# FSR_amp_v0_1.net
KiCad netlist of a schematic drawn in EAGLE
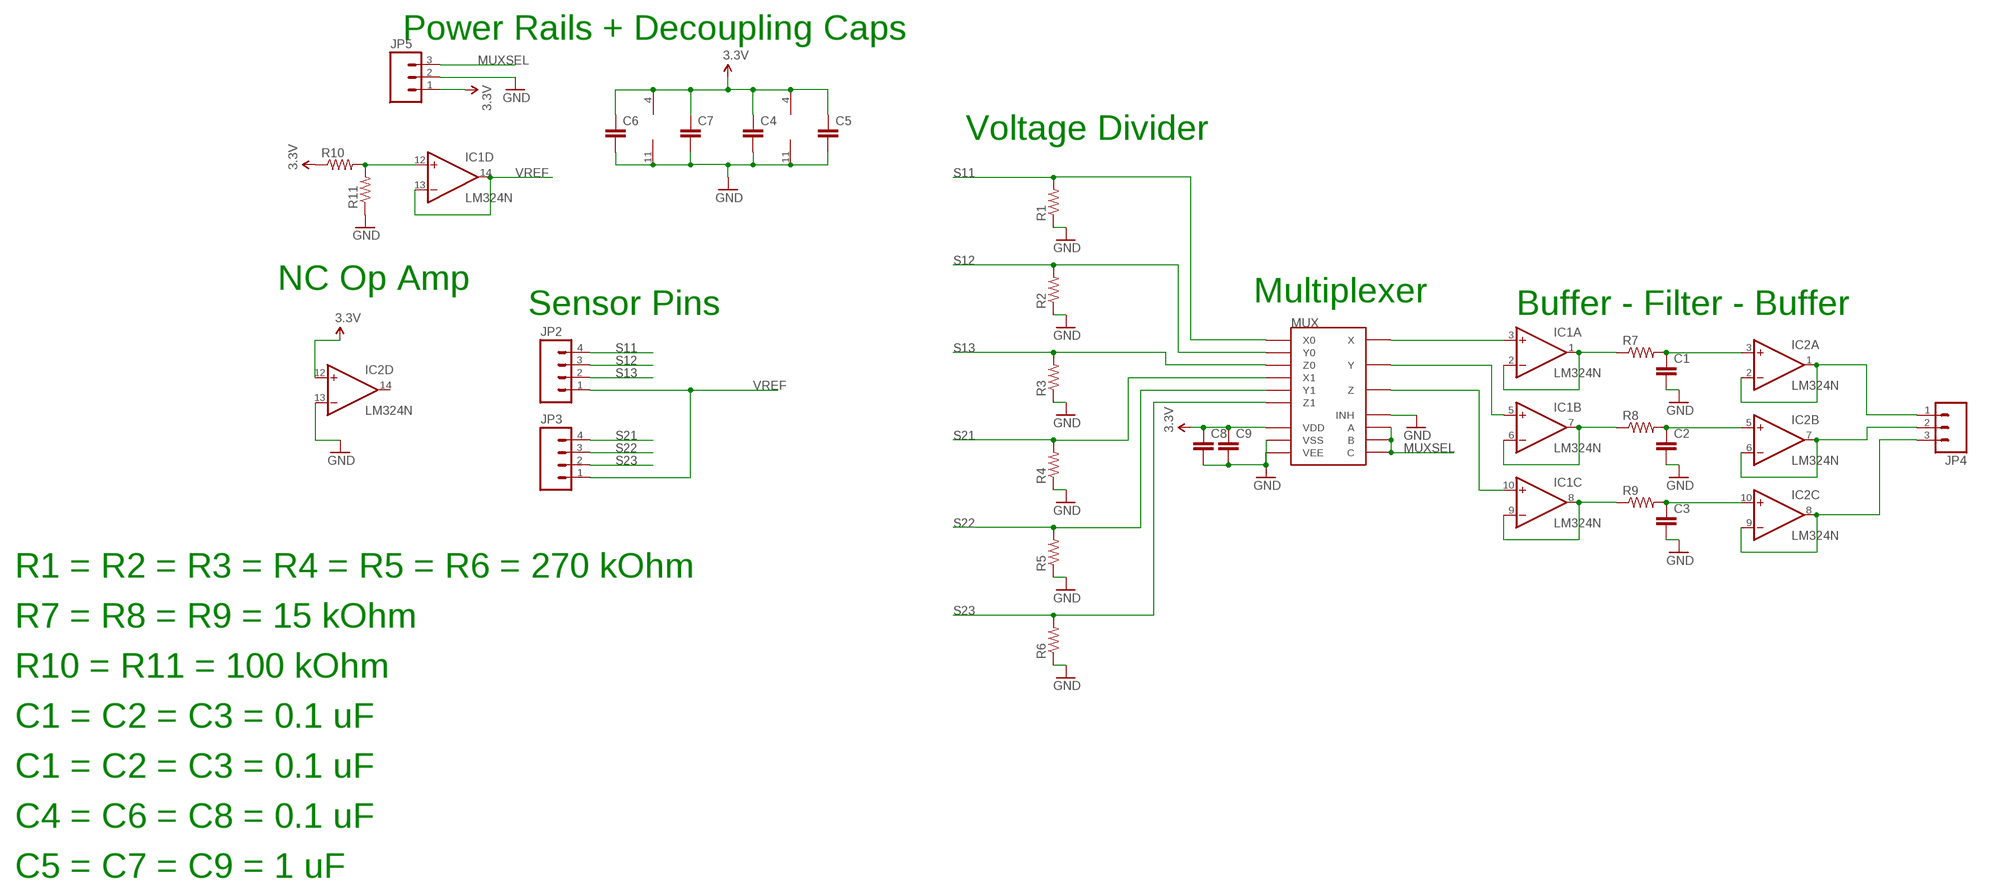
[diagram p0: schematic, sheet 1]

(export (version "E")
  (design (tool "Eeschema 10.0.6"))
  (components
    (comp (ref "C1")
      (value "CAPPTH")
      (footprint "eagle-import:CAP-PTH-SMALL")
      (libsource (lib "eagle-import") (part "CAPPTH"))
    )
    (comp (ref "C2")
      (value "CAPPTH")
      (footprint "eagle-import:CAP-PTH-SMALL")
      (libsource (lib "eagle-import") (part "CAPPTH"))
    )
    (comp (ref "C3")
      (value "CAPPTH")
      (footprint "eagle-import:CAP-PTH-SMALL")
      (libsource (lib "eagle-import") (part "CAPPTH"))
    )
    (comp (ref "C4")
      (value "CAPPTH")
      (footprint "eagle-import:CAP-PTH-SMALL")
      (libsource (lib "eagle-import") (part "CAPPTH"))
    )
    (comp (ref "C5")
      (value "CAPPTH")
      (footprint "eagle-import:CAP-PTH-SMALL")
      (libsource (lib "eagle-import") (part "CAPPTH"))
    )
    (comp (ref "C6")
      (value "CAPPTH")
      (footprint "eagle-import:CAP-PTH-SMALL")
      (libsource (lib "eagle-import") (part "CAPPTH"))
    )
    (comp (ref "C7")
      (value "CAPPTH")
      (footprint "eagle-import:CAP-PTH-SMALL")
      (libsource (lib "eagle-import") (part "CAPPTH"))
    )
    (comp (ref "C8")
      (value "CAPPTH")
      (footprint "eagle-import:CAP-PTH-SMALL")
      (libsource (lib "eagle-import") (part "CAPPTH"))
    )
    (comp (ref "C9")
      (value "CAPPTH")
      (footprint "eagle-import:CAP-PTH-SMALL")
      (libsource (lib "eagle-import") (part "CAPPTH"))
    )
    (comp (ref "IC1")
      (value "LM324N")
      (footprint "eagle-import:DIL14")
      (libsource (lib "eagle-import") (part "LM324N"))
    )
    (comp (ref "IC2")
      (value "LM324N")
      (footprint "eagle-import:DIL14")
      (libsource (lib "eagle-import") (part "LM324N"))
    )
    (comp (ref "JP2")
      (value "M04POLAR")
      (footprint "eagle-import:MOLEX-1X4")
      (libsource (lib "eagle-import") (part "M04POLAR"))
    )
    (comp (ref "JP3")
      (value "M04POLAR")
      (footprint "eagle-import:MOLEX-1X4")
      (libsource (lib "eagle-import") (part "M04POLAR"))
    )
    (comp (ref "JP4")
      (value "M03POLAR")
      (footprint "eagle-import:MOLEX-1X3")
      (libsource (lib "eagle-import") (part "M03POLAR"))
    )
    (comp (ref "JP5")
      (value "M03POLAR")
      (footprint "eagle-import:MOLEX-1X3")
      (libsource (lib "eagle-import") (part "M03POLAR"))
    )
    (comp (ref "MUX")
      (value "MC14053BCPDIL16")
      (footprint "eagle-import:DIL16")
      (libsource (lib "eagle-import") (part "MC14053BCPDIL16"))
    )
    (comp (ref "R1")
      (value "R-US_0207/10")
      (footprint "eagle-import:0207_10")
      (libsource (lib "eagle-import") (part "R-US_0207/10"))
    )
    (comp (ref "R2")
      (value "R-US_0207/10")
      (footprint "eagle-import:0207_10")
      (libsource (lib "eagle-import") (part "R-US_0207/10"))
    )
    (comp (ref "R3")
      (value "R-US_0207/10")
      (footprint "eagle-import:0207_10")
      (libsource (lib "eagle-import") (part "R-US_0207/10"))
    )
    (comp (ref "R4")
      (value "R-US_0207/10")
      (footprint "eagle-import:0207_10")
      (libsource (lib "eagle-import") (part "R-US_0207/10"))
    )
    (comp (ref "R5")
      (value "R-US_0207/10")
      (footprint "eagle-import:0207_10")
      (libsource (lib "eagle-import") (part "R-US_0207/10"))
    )
    (comp (ref "R6")
      (value "R-US_0207/10")
      (footprint "eagle-import:0207_10")
      (libsource (lib "eagle-import") (part "R-US_0207/10"))
    )
    (comp (ref "R7")
      (value "R-US_0207/10")
      (footprint "eagle-import:0207_10")
      (libsource (lib "eagle-import") (part "R-US_0207/10"))
    )
    (comp (ref "R8")
      (value "R-US_0207/10")
      (footprint "eagle-import:0207_10")
      (libsource (lib "eagle-import") (part "R-US_0207/10"))
    )
    (comp (ref "R9")
      (value "R-US_0207/10")
      (footprint "eagle-import:0207_10")
      (libsource (lib "eagle-import") (part "R-US_0207/10"))
    )
    (comp (ref "R10")
      (value "R-US_0207/10")
      (footprint "eagle-import:0207_10")
      (libsource (lib "eagle-import") (part "R-US_0207/10"))
    )
    (comp (ref "R11")
      (value "R-US_0207/10")
      (footprint "eagle-import:0207_10")
      (libsource (lib "eagle-import") (part "R-US_0207/10"))
    )
  )
  (nets
    (net (code "1") (name "/MUXSEL") (class "Default")
      (node (ref "JP5") (pin "3") (pinfunction "3_3") (pintype "passive"))
      (node (ref "MUX") (pin "10") (pinfunction "B_10") (pintype "bidirectional"))
      (node (ref "MUX") (pin "11") (pinfunction "A_11") (pintype "bidirectional"))
      (node (ref "MUX") (pin "9") (pinfunction "C_9") (pintype "bidirectional"))
    )
    (net (code "2") (name "/S11") (class "Default")
      (node (ref "JP2") (pin "4") (pinfunction "4_4") (pintype "passive"))
      (node (ref "MUX") (pin "12") (pinfunction "X0_12") (pintype "bidirectional"))
      (node (ref "R1") (pin "2") (pinfunction "2_2") (pintype "passive"))
    )
    (net (code "3") (name "/S12") (class "Default")
      (node (ref "JP2") (pin "3") (pinfunction "3_3") (pintype "passive"))
      (node (ref "MUX") (pin "2") (pinfunction "Y0_2") (pintype "bidirectional"))
      (node (ref "R2") (pin "2") (pinfunction "2_2") (pintype "passive"))
    )
    (net (code "4") (name "/S13") (class "Default")
      (node (ref "JP2") (pin "2") (pinfunction "2_2") (pintype "passive"))
      (node (ref "MUX") (pin "5") (pinfunction "Z0_5") (pintype "bidirectional"))
      (node (ref "R3") (pin "2") (pinfunction "2_2") (pintype "passive"))
    )
    (net (code "5") (name "/S21") (class "Default")
      (node (ref "JP3") (pin "4") (pinfunction "4_4") (pintype "passive"))
      (node (ref "MUX") (pin "13") (pinfunction "X1_13") (pintype "bidirectional"))
      (node (ref "R4") (pin "2") (pinfunction "2_2") (pintype "passive"))
    )
    (net (code "6") (name "/S22") (class "Default")
      (node (ref "JP3") (pin "3") (pinfunction "3_3") (pintype "passive"))
      (node (ref "MUX") (pin "1") (pinfunction "Y1_1") (pintype "bidirectional"))
      (node (ref "R5") (pin "2") (pinfunction "2_2") (pintype "passive"))
    )
    (net (code "7") (name "/S23") (class "Default")
      (node (ref "JP3") (pin "2") (pinfunction "2_2") (pintype "passive"))
      (node (ref "MUX") (pin "3") (pinfunction "Z1_3") (pintype "bidirectional"))
      (node (ref "R6") (pin "2") (pinfunction "2_2") (pintype "passive"))
    )
    (net (code "8") (name "/VREF") (class "Default")
      (node (ref "IC1") (pin "13") (pinfunction "-IN_13") (pintype "input"))
      (node (ref "IC1") (pin "14") (pinfunction "OUT_14") (pintype "output"))
      (node (ref "JP2") (pin "1") (pinfunction "1_1") (pintype "passive"))
      (node (ref "JP3") (pin "1") (pinfunction "1_1") (pintype "passive"))
    )
    (net (code "9") (name "3.3V") (class "Default")
      (node (ref "C4") (pin "1") (pinfunction "1_1") (pintype "passive"))
      (node (ref "C5") (pin "1") (pinfunction "1_1") (pintype "passive"))
      (node (ref "C6") (pin "1") (pinfunction "1_1") (pintype "passive"))
      (node (ref "C7") (pin "1") (pinfunction "1_1") (pintype "passive"))
      (node (ref "C8") (pin "1") (pinfunction "1_1") (pintype "passive"))
      (node (ref "C9") (pin "1") (pinfunction "1_1") (pintype "passive"))
      (node (ref "IC1") (pin "4") (pinfunction "V+_4") (pintype "power_in"))
      (node (ref "IC2") (pin "12") (pinfunction "+IN_12") (pintype "input"))
      (node (ref "IC2") (pin "4") (pinfunction "V+_4") (pintype "power_in"))
      (node (ref "JP5") (pin "1") (pinfunction "1_1") (pintype "passive"))
      (node (ref "MUX") (pin "16") (pinfunction "VDD_16") (pintype "bidirectional"))
      (node (ref "R10") (pin "1") (pinfunction "1_1") (pintype "passive"))
    )
    (net (code "10") (name "GND") (class "Default")
      (node (ref "C1") (pin "2") (pinfunction "2_2") (pintype "passive"))
      (node (ref "C2") (pin "2") (pinfunction "2_2") (pintype "passive"))
      (node (ref "C3") (pin "2") (pinfunction "2_2") (pintype "passive"))
      (node (ref "C4") (pin "2") (pinfunction "2_2") (pintype "passive"))
      (node (ref "C5") (pin "2") (pinfunction "2_2") (pintype "passive"))
      (node (ref "C6") (pin "2") (pinfunction "2_2") (pintype "passive"))
      (node (ref "C7") (pin "2") (pinfunction "2_2") (pintype "passive"))
      (node (ref "C8") (pin "2") (pinfunction "2_2") (pintype "passive"))
      (node (ref "C9") (pin "2") (pinfunction "2_2") (pintype "passive"))
      (node (ref "IC1") (pin "11") (pinfunction "V-_11") (pintype "power_in"))
      (node (ref "IC2") (pin "11") (pinfunction "V-_11") (pintype "power_in"))
      (node (ref "IC2") (pin "13") (pinfunction "-IN_13") (pintype "input"))
      (node (ref "JP5") (pin "2") (pinfunction "2_2") (pintype "passive"))
      (node (ref "MUX") (pin "6") (pinfunction "INH_6") (pintype "bidirectional"))
      (node (ref "MUX") (pin "7") (pinfunction "VEE_7") (pintype "bidirectional"))
      (node (ref "MUX") (pin "8") (pinfunction "VSS_8") (pintype "bidirectional"))
      (node (ref "R1") (pin "1") (pinfunction "1_1") (pintype "passive"))
      (node (ref "R11") (pin "1") (pinfunction "1_1") (pintype "passive"))
      (node (ref "R2") (pin "1") (pinfunction "1_1") (pintype "passive"))
      (node (ref "R3") (pin "1") (pinfunction "1_1") (pintype "passive"))
      (node (ref "R4") (pin "1") (pinfunction "1_1") (pintype "passive"))
      (node (ref "R5") (pin "1") (pinfunction "1_1") (pintype "passive"))
      (node (ref "R6") (pin "1") (pinfunction "1_1") (pintype "passive"))
    )
    (net (code "11") (name "Net-(IC1A-+IN)") (class "Default")
      (node (ref "IC1") (pin "3") (pinfunction "+IN_3") (pintype "input"))
      (node (ref "MUX") (pin "14") (pinfunction "X_14") (pintype "bidirectional"))
    )
    (net (code "12") (name "Net-(IC1A--IN)") (class "Default")
      (node (ref "IC1") (pin "1") (pinfunction "OUT_1") (pintype "output"))
      (node (ref "IC1") (pin "2") (pinfunction "-IN_2") (pintype "input"))
      (node (ref "R7") (pin "1") (pinfunction "1_1") (pintype "passive"))
    )
    (net (code "13") (name "Net-(IC1B-+IN)") (class "Default")
      (node (ref "IC1") (pin "5") (pinfunction "+IN_5") (pintype "input"))
      (node (ref "MUX") (pin "15") (pinfunction "Y_15") (pintype "bidirectional"))
    )
    (net (code "14") (name "Net-(IC1B--IN)") (class "Default")
      (node (ref "IC1") (pin "6") (pinfunction "-IN_6") (pintype "input"))
      (node (ref "IC1") (pin "7") (pinfunction "OUT_7") (pintype "output"))
      (node (ref "R8") (pin "1") (pinfunction "1_1") (pintype "passive"))
    )
    (net (code "15") (name "Net-(IC1C-+IN)") (class "Default")
      (node (ref "IC1") (pin "10") (pinfunction "+IN_10") (pintype "input"))
      (node (ref "MUX") (pin "4") (pinfunction "Z_4") (pintype "bidirectional"))
    )
    (net (code "16") (name "Net-(IC1C--IN)") (class "Default")
      (node (ref "IC1") (pin "8") (pinfunction "OUT_8") (pintype "output"))
      (node (ref "IC1") (pin "9") (pinfunction "-IN_9") (pintype "input"))
      (node (ref "R9") (pin "1") (pinfunction "1_1") (pintype "passive"))
    )
    (net (code "17") (name "Net-(IC1D-+IN)") (class "Default")
      (node (ref "IC1") (pin "12") (pinfunction "+IN_12") (pintype "input"))
      (node (ref "R10") (pin "2") (pinfunction "2_2") (pintype "passive"))
      (node (ref "R11") (pin "2") (pinfunction "2_2") (pintype "passive"))
    )
    (net (code "18") (name "Net-(IC2A-+IN)") (class "Default")
      (node (ref "C1") (pin "1") (pinfunction "1_1") (pintype "passive"))
      (node (ref "IC2") (pin "3") (pinfunction "+IN_3") (pintype "input"))
      (node (ref "R7") (pin "2") (pinfunction "2_2") (pintype "passive"))
    )
    (net (code "19") (name "Net-(IC2A--IN)") (class "Default")
      (node (ref "IC2") (pin "1") (pinfunction "OUT_1") (pintype "output"))
      (node (ref "IC2") (pin "2") (pinfunction "-IN_2") (pintype "input"))
      (node (ref "JP4") (pin "1") (pinfunction "1_1") (pintype "passive"))
    )
    (net (code "20") (name "Net-(IC2B-+IN)") (class "Default")
      (node (ref "C2") (pin "1") (pinfunction "1_1") (pintype "passive"))
      (node (ref "IC2") (pin "5") (pinfunction "+IN_5") (pintype "input"))
      (node (ref "R8") (pin "2") (pinfunction "2_2") (pintype "passive"))
    )
    (net (code "21") (name "Net-(IC2B--IN)") (class "Default")
      (node (ref "IC2") (pin "6") (pinfunction "-IN_6") (pintype "input"))
      (node (ref "IC2") (pin "7") (pinfunction "OUT_7") (pintype "output"))
      (node (ref "JP4") (pin "2") (pinfunction "2_2") (pintype "passive"))
    )
    (net (code "22") (name "Net-(IC2C-+IN)") (class "Default")
      (node (ref "C3") (pin "1") (pinfunction "1_1") (pintype "passive"))
      (node (ref "IC2") (pin "10") (pinfunction "+IN_10") (pintype "input"))
      (node (ref "R9") (pin "2") (pinfunction "2_2") (pintype "passive"))
    )
    (net (code "23") (name "Net-(IC2C--IN)") (class "Default")
      (node (ref "IC2") (pin "8") (pinfunction "OUT_8") (pintype "output"))
      (node (ref "IC2") (pin "9") (pinfunction "-IN_9") (pintype "input"))
      (node (ref "JP4") (pin "3") (pinfunction "3_3") (pintype "passive"))
    )
    (net (code "24") (name "unconnected-(IC2D-OUT-Pad14)") (class "Default")
      (node (ref "IC2") (pin "14") (pinfunction "OUT_14") (pintype "output"))
    )
  )
)
